# LCmeter0-LCD-8pinlcd-PIC_COMP.net
KiCad netlist of a schematic drawn in EAGLE
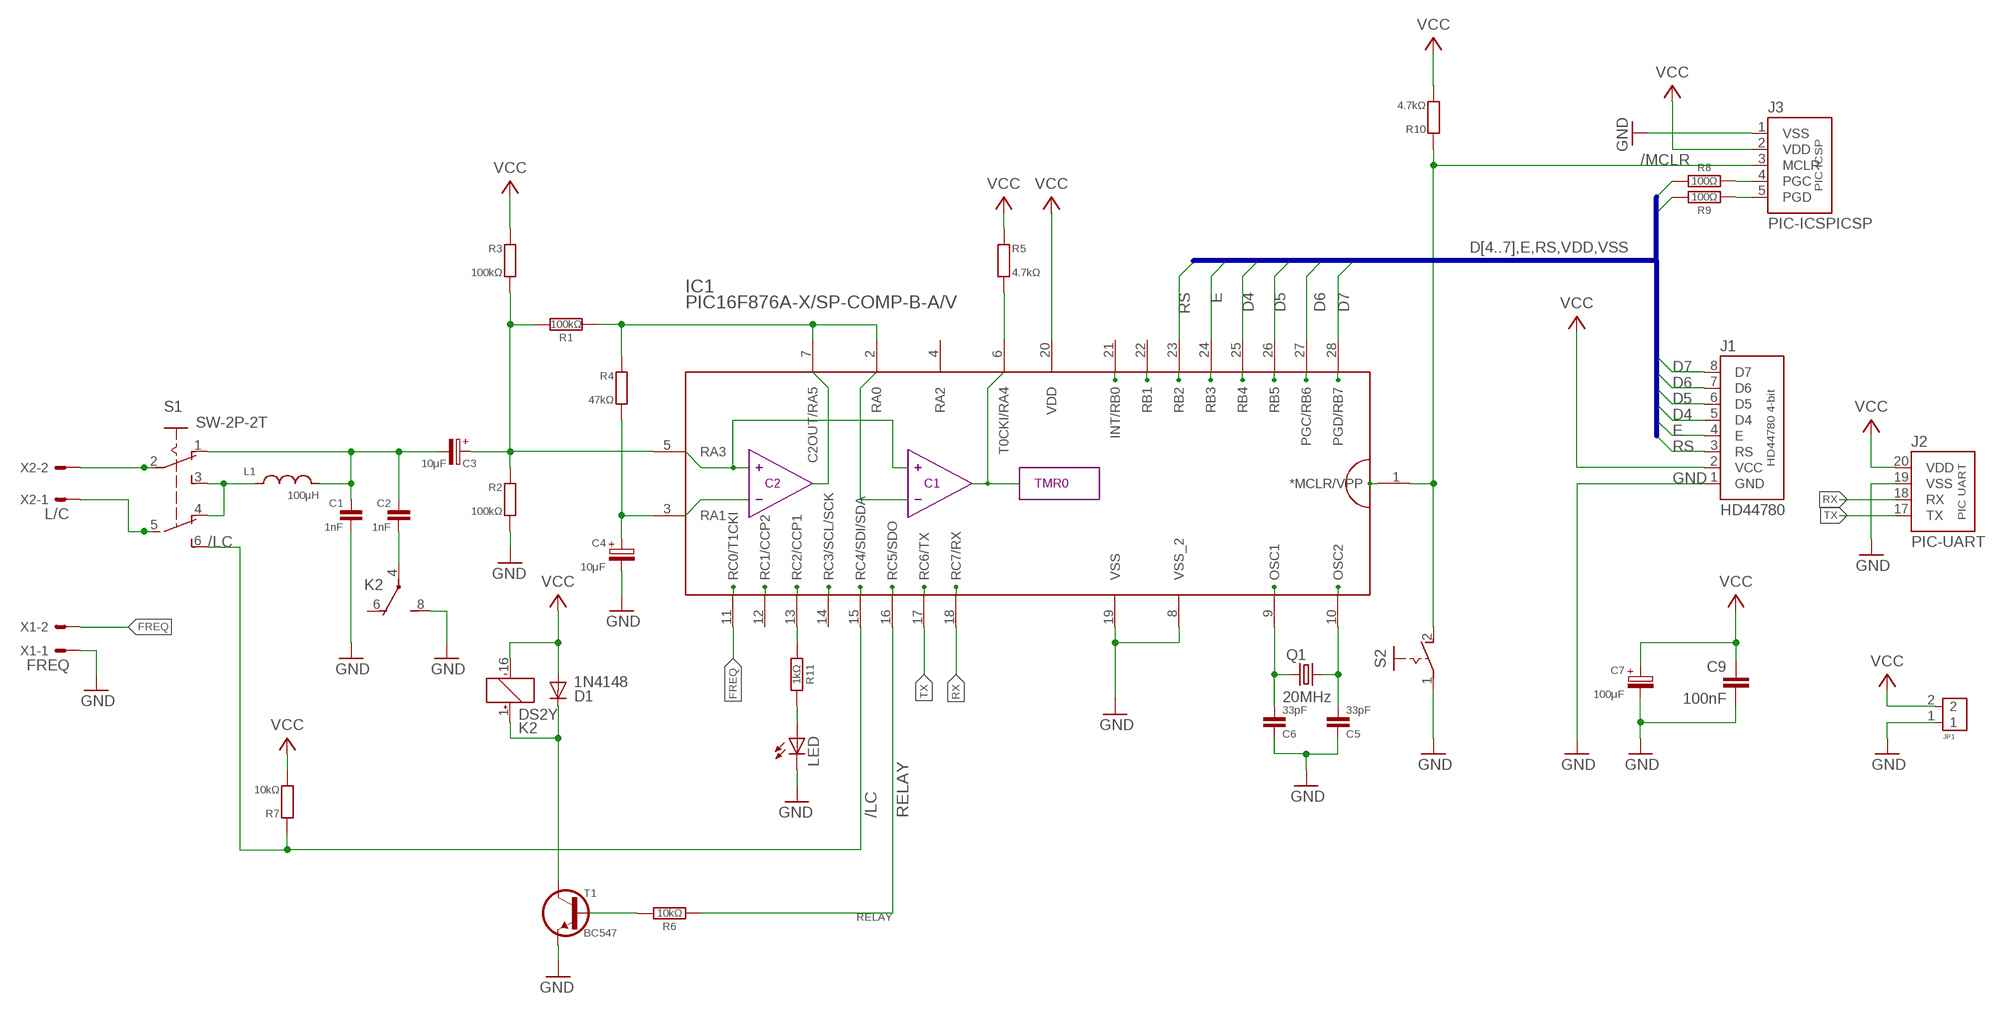
[diagram p0: schematic, sheet 1]

(export (version "E")
  (design (tool "Eeschema 10.0.6"))
  (components
    (comp (ref "C1")
      (value "1nF")
      (footprint "eagle-import:C050-020X036")
      (libsource (lib "eagle-import") (part "C050-020X036"))
    )
    (comp (ref "C2")
      (value "1nF")
      (footprint "eagle-import:C050-020X036")
      (libsource (lib "eagle-import") (part "C050-020X036"))
    )
    (comp (ref "C3")
      (value "10μF")
      (footprint "eagle-import:E2,5-4")
      (libsource (lib "eagle-import") (part "CPOL-HE2,5-4"))
    )
    (comp (ref "C4")
      (value "10μF")
      (footprint "eagle-import:E2,5-4")
      (libsource (lib "eagle-import") (part "CPOLE2,5-4"))
    )
    (comp (ref "C5")
      (value "33pF")
      (footprint "eagle-import:C025-020X036")
      (libsource (lib "eagle-import") (part "C025-020X036"))
    )
    (comp (ref "C6")
      (value "33pF")
      (footprint "eagle-import:C025-020X036")
      (libsource (lib "eagle-import") (part "C025-020X036"))
    )
    (comp (ref "C7")
      (value "100μF")
      (footprint "eagle-import:E2,5-5")
      (libsource (lib "eagle-import") (part "CPOLE2.5-5"))
    )
    (comp (ref "C9")
      (value "100nF")
      (footprint "eagle-import:C025-024X044")
      (libsource (lib "eagle-import") (part "C-EU025-024X044"))
    )
    (comp (ref "D1")
      (value "1N4148")
      (footprint "eagle-import:DO34-7")
      (libsource (lib "eagle-import") (part "1N414834-7"))
    )
    (comp (ref "IC1")
      (value "PIC16F876A-X/SP-COMP-B-A/V")
      (footprint "eagle-import:DIL28-3_V")
      (libsource (lib "eagle-import") (part "PIC16F876A-X/SP-COMP-B-A/V"))
    )
    (comp (ref "J1")
      (value "HD44780")
      (footprint "eagle-import:CONN-8P")
      (libsource (lib "eagle-import") (part "HD44780-4BIT-8PIN"))
    )
    (comp (ref "J2")
      (value "PIC-UART")
      (footprint "eagle-import:PIC-UART")
      (libsource (lib "eagle-import") (part "PIC-UART"))
    )
    (comp (ref "J3")
      (value "PIC-ICSPICSP")
      (footprint "eagle-import:PIC-ICSP")
      (libsource (lib "eagle-import") (part "PIC-ICSPICSP"))
    )
    (comp (ref "JP1")
      (value "CONN-2P2P/V")
      (footprint "eagle-import:CONN-2P-V")
      (libsource (lib "eagle-import") (part "CONN-2P2P/V"))
    )
    (comp (ref "K2")
      (value "DS2Y")
      (footprint "eagle-import:DS2Y")
      (fields (field (name "MPN") "DS2Y-S-DC5V"))
      (libsource (lib "eagle-import") (part "DS2Y-S-DC5V"))
    )
    (comp (ref "L1")
      (value "100µH")
      (footprint "eagle-import:L-02_5V")
      (libsource (lib "eagle-import") (part "L-SHORT02/5"))
    )
    (comp (ref "LED")
      (value "TLLG4400")
      (footprint "eagle-import:LED3MM")
      (fields (field (name "MF") "VISHAY SEMICONDUCTOR"))
      (libsource (lib "eagle-import") (part "TLLG4400"))
    )
    (comp (ref "Q1")
      (value "20MHz")
      (footprint "eagle-import:HC49")
      (libsource (lib "eagle-import") (part "CRYSTALHC49"))
    )
    (comp (ref "R1")
      (value "100kΩ")
      (footprint "eagle-import:0202_7")
      (libsource (lib "eagle-import") (part "R-H0202/7"))
    )
    (comp (ref "R2")
      (value "100kΩ")
      (footprint "eagle-import:0202_7")
      (libsource (lib "eagle-import") (part "R0202/7"))
    )
    (comp (ref "R3")
      (value "100kΩ")
      (footprint "eagle-import:0202_7")
      (libsource (lib "eagle-import") (part "R0202/7"))
    )
    (comp (ref "R4")
      (value "47kΩ")
      (footprint "eagle-import:0202_7")
      (libsource (lib "eagle-import") (part "R0202/7"))
    )
    (comp (ref "R5")
      (value "4.7kΩ")
      (footprint "eagle-import:0202_7")
      (libsource (lib "eagle-import") (part "R0202/7"))
    )
    (comp (ref "R6")
      (value "10kΩ")
      (footprint "eagle-import:0202_7")
      (libsource (lib "eagle-import") (part "R-H0202/7"))
    )
    (comp (ref "R7")
      (value "10kΩ")
      (footprint "eagle-import:0202_10")
      (libsource (lib "eagle-import") (part "R0202/10"))
    )
    (comp (ref "R8")
      (value "100Ω")
      (footprint "eagle-import:0202_5")
      (libsource (lib "eagle-import") (part "R-H0202/5"))
    )
    (comp (ref "R9")
      (value "100Ω")
      (footprint "eagle-import:0202_5")
      (libsource (lib "eagle-import") (part "R-H0202/5"))
    )
    (comp (ref "R10")
      (value "4.7kΩ")
      (footprint "eagle-import:0202_7")
      (libsource (lib "eagle-import") (part "R0202/7"))
    )
    (comp (ref "R11")
      (value "1kΩ")
      (footprint "eagle-import:0202_5")
      (libsource (lib "eagle-import") (part "R-H0202/5"))
    )
    (comp (ref "S1")
      (value "SW-2P-2T")
      (footprint "eagle-import:SLSW-2P2T")
      (libsource (lib "eagle-import") (part "SW-2P-2T"))
    )
    (comp (ref "S2")
      (value "PB-1P-1T")
      (footprint "eagle-import:PB-1P1T")
      (libsource (lib "eagle-import") (part "PB-1P-1T"))
    )
    (comp (ref "T1")
      (value "BC547")
      (footprint "eagle-import:TO92-CBE-A")
      (libsource (lib "eagle-import") (part "BC547CBE-A"))
    )
    (comp (ref "X1")
      (value "FREQ")
      (footprint "eagle-import:70543-02")
      (libsource (lib "eagle-import") (part "C-GRID-02-70543"))
    )
    (comp (ref "X2")
      (value "L/C")
      (footprint "eagle-import:70543-02")
      (libsource (lib "eagle-import") (part "C-GRID-02-70543"))
    )
  )
  (nets
    (net (code "3") (name "/D4") (class "Default")
      (node (ref "IC1") (pin "25") (pinfunction "RB4_25") (pintype "passive"))
      (node (ref "J1") (pin "5") (pinfunction "D4_5") (pintype "passive"))
    )
    (net (code "4") (name "/D5") (class "Default")
      (node (ref "IC1") (pin "26") (pinfunction "RB5_26") (pintype "passive"))
      (node (ref "J1") (pin "6") (pinfunction "D5_6") (pintype "passive"))
    )
    (net (code "5") (name "/D6") (class "Default")
      (node (ref "IC1") (pin "27") (pinfunction "PGC/RB6_27") (pintype "passive"))
      (node (ref "J1") (pin "7") (pinfunction "D6_7") (pintype "passive"))
      (node (ref "R9") (pin "1") (pinfunction "1_1") (pintype "passive"))
    )
    (net (code "6") (name "/D7") (class "Default")
      (node (ref "IC1") (pin "28") (pinfunction "PGD/RB7_28") (pintype "passive"))
      (node (ref "J1") (pin "8") (pinfunction "D7_8") (pintype "passive"))
      (node (ref "R8") (pin "1") (pinfunction "1_1") (pintype "passive"))
    )
    (net (code "7") (name "/E") (class "Default")
      (node (ref "IC1") (pin "24") (pinfunction "RB3_24") (pintype "passive"))
      (node (ref "J1") (pin "4") (pinfunction "E_4") (pintype "passive"))
    )
    (net (code "8") (name "/RELAY") (class "Default")
      (node (ref "IC1") (pin "16") (pinfunction "RC5/SDO_16") (pintype "passive"))
      (node (ref "R6") (pin "2") (pinfunction "2_2") (pintype "passive"))
    )
    (net (code "9") (name "/RS") (class "Default")
      (node (ref "IC1") (pin "23") (pinfunction "RB2_23") (pintype "passive"))
      (node (ref "J1") (pin "3") (pinfunction "RS_3") (pintype "passive"))
    )
    (net (code "11") (name "/{slash}LC") (class "Default")
      (node (ref "IC1") (pin "15") (pinfunction "RC4/SDI/SDA_15") (pintype "passive"))
      (node (ref "R7") (pin "1") (pinfunction "1_1") (pintype "passive"))
      (node (ref "S1") (pin "6") (pinfunction "S1_6") (pintype "passive"))
    )
    (net (code "12") (name "/{slash}MCLR") (class "Default")
      (node (ref "IC1") (pin "1") (pinfunction "*MCLR/VPP_1") (pintype "passive"))
      (node (ref "J3") (pin "3") (pinfunction "MCLR_3") (pintype "passive"))
      (node (ref "R10") (pin "1") (pinfunction "1_1") (pintype "passive"))
      (node (ref "S2") (pin "2") (pinfunction "S_2") (pintype "passive"))
    )
    (net (code "13") (name "FREQ") (class "Default")
      (node (ref "IC1") (pin "11") (pinfunction "RC0/T1CKI_11") (pintype "passive"))
      (node (ref "X1") (pin "2") (pinfunction "S_2") (pintype "passive"))
    )
    (net (code "14") (name "GND") (class "Default")
      (node (ref "C1") (pin "2") (pinfunction "2_2") (pintype "passive"))
      (node (ref "C4") (pin "-") (pinfunction "-_-") (pintype "passive"))
      (node (ref "C5") (pin "1") (pinfunction "1_1") (pintype "passive"))
      (node (ref "C6") (pin "1") (pinfunction "1_1") (pintype "passive"))
      (node (ref "C7") (pin "-") (pinfunction "-_-") (pintype "passive"))
      (node (ref "C9") (pin "2") (pinfunction "2_2") (pintype "passive"))
      (node (ref "IC1") (pin "19") (pinfunction "VSS_19") (pintype "passive"))
      (node (ref "IC1") (pin "8") (pinfunction "VSS_2_8") (pintype "passive"))
      (node (ref "J1") (pin "1") (pinfunction "GND_1") (pintype "passive"))
      (node (ref "J2") (pin "19") (pinfunction "VSS_19") (pintype "passive"))
      (node (ref "J3") (pin "1") (pinfunction "VSS_1") (pintype "passive"))
      (node (ref "JP1") (pin "1") (pinfunction "1_1") (pintype "bidirectional"))
      (node (ref "K2") (pin "8") (pinfunction "S_8") (pintype "passive"))
      (node (ref "LED") (pin "K") (pinfunction "C_K") (pintype "passive"))
      (node (ref "R2") (pin "2") (pinfunction "2_2") (pintype "passive"))
      (node (ref "S2") (pin "1") (pinfunction "P_1") (pintype "passive"))
      (node (ref "T1") (pin "E") (pinfunction "E_E") (pintype "passive"))
      (node (ref "X1") (pin "1") (pinfunction "S_1") (pintype "passive"))
    )
    (net (code "15") (name "Net-(IC1-C2OUT{slash}RA5)") (class "Default")
      (node (ref "IC1") (pin "2") (pinfunction "RA0_2") (pintype "passive"))
      (node (ref "IC1") (pin "7") (pinfunction "C2OUT/RA5_7") (pintype "passive"))
      (node (ref "R1") (pin "1") (pinfunction "1_1") (pintype "passive"))
      (node (ref "R4") (pin "1") (pinfunction "1_1") (pintype "passive"))
    )
    (net (code "16") (name "Net-(IC1-OSC1)") (class "Default")
      (node (ref "C6") (pin "2") (pinfunction "2_2") (pintype "passive"))
      (node (ref "IC1") (pin "9") (pinfunction "OSC1_9") (pintype "passive"))
      (node (ref "Q1") (pin "1") (pinfunction "1_1") (pintype "passive"))
    )
    (net (code "17") (name "Net-(IC1-OSC2)") (class "Default")
      (node (ref "C5") (pin "2") (pinfunction "2_2") (pintype "passive"))
      (node (ref "IC1") (pin "10") (pinfunction "OSC2_10") (pintype "passive"))
      (node (ref "Q1") (pin "2") (pinfunction "2_2") (pintype "passive"))
    )
    (net (code "18") (name "Net-(IC1-RA1)") (class "Default")
      (node (ref "C4") (pin "+") (pinfunction "+_+") (pintype "passive"))
      (node (ref "IC1") (pin "3") (pinfunction "RA1_3") (pintype "passive"))
      (node (ref "R4") (pin "2") (pinfunction "2_2") (pintype "passive"))
    )
    (net (code "19") (name "Net-(IC1-RA3)") (class "Default")
      (node (ref "C3") (pin "+") (pinfunction "+_+") (pintype "passive"))
      (node (ref "IC1") (pin "5") (pinfunction "RA3_5") (pintype "passive"))
      (node (ref "R1") (pin "2") (pinfunction "2_2") (pintype "passive"))
      (node (ref "R2") (pin "1") (pinfunction "1_1") (pintype "passive"))
      (node (ref "R3") (pin "2") (pinfunction "2_2") (pintype "passive"))
    )
    (net (code "20") (name "Net-(IC1-RC2{slash}CCP1)") (class "Default")
      (node (ref "IC1") (pin "13") (pinfunction "RC2/CCP1_13") (pintype "passive"))
      (node (ref "R11") (pin "2") (pinfunction "2_2") (pintype "passive"))
    )
    (net (code "21") (name "Net-(IC1-T0CKI{slash}RA4)") (class "Default")
      (node (ref "IC1") (pin "6") (pinfunction "T0CKI/RA4_6") (pintype "passive"))
      (node (ref "R5") (pin "2") (pinfunction "2_2") (pintype "passive"))
    )
    (net (code "22") (name "Net-(J3-PGC)") (class "Default")
      (node (ref "J3") (pin "4") (pinfunction "PGC_4") (pintype "passive"))
      (node (ref "R8") (pin "2") (pinfunction "2_2") (pintype "passive"))
    )
    (net (code "23") (name "Net-(J3-PGD)") (class "Default")
      (node (ref "J3") (pin "5") (pinfunction "PGD_5") (pintype "passive"))
      (node (ref "R9") (pin "2") (pinfunction "2_2") (pintype "passive"))
    )
    (net (code "24") (name "Net-(K2A-+)") (class "Default")
      (node (ref "D1") (pin "C") (pinfunction "C_C") (pintype "passive"))
      (node (ref "K2") (pin "1") (pinfunction "+_1") (pintype "passive"))
      (node (ref "T1") (pin "C") (pinfunction "C_C") (pintype "passive"))
    )
    (net (code "25") (name "Net-(K2B-P)") (class "Default")
      (node (ref "C2") (pin "2") (pinfunction "2_2") (pintype "passive"))
      (node (ref "K2") (pin "4") (pinfunction "P_4") (pintype "passive"))
    )
    (net (code "26") (name "Net-(LED-PadA)") (class "Default")
      (node (ref "LED") (pin "A") (pinfunction "A_A") (pintype "passive"))
      (node (ref "R11") (pin "1") (pinfunction "1_1") (pintype "passive"))
    )
    (net (code "27") (name "Net-(R6-Pad1)") (class "Default")
      (node (ref "R6") (pin "1") (pinfunction "1_1") (pintype "passive"))
      (node (ref "T1") (pin "B") (pinfunction "B_B") (pintype "passive"))
    )
    (net (code "28") (name "Net-(S1-O)") (class "Default")
      (node (ref "C1") (pin "1") (pinfunction "1_1") (pintype "passive"))
      (node (ref "C2") (pin "1") (pinfunction "1_1") (pintype "passive"))
      (node (ref "C3") (pin "-") (pinfunction "-_-") (pintype "passive"))
      (node (ref "L1") (pin "2") (pinfunction "2_2") (pintype "passive"))
      (node (ref "S1") (pin "1") (pinfunction "O_1") (pintype "passive"))
    )
    (net (code "29") (name "Net-(S1-O1)") (class "Default")
      (node (ref "L1") (pin "1") (pinfunction "1_1") (pintype "passive"))
      (node (ref "S1") (pin "3") (pinfunction "S_3") (pintype "passive"))
      (node (ref "S1") (pin "4") (pinfunction "O1_4") (pintype "passive"))
    )
    (net (code "30") (name "Net-(S1-P)") (class "Default")
      (node (ref "S1") (pin "2") (pinfunction "P_2") (pintype "passive"))
      (node (ref "X2") (pin "2") (pinfunction "S_2") (pintype "passive"))
    )
    (net (code "31") (name "Net-(S1-P1)") (class "Default")
      (node (ref "S1") (pin "5") (pinfunction "P1_5") (pintype "passive"))
      (node (ref "X2") (pin "1") (pinfunction "S_1") (pintype "passive"))
    )
    (net (code "32") (name "RX") (class "Default")
      (node (ref "IC1") (pin "18") (pinfunction "RC7/RX_18") (pintype "passive"))
      (node (ref "J2") (pin "18") (pinfunction "RX_18") (pintype "passive"))
    )
    (net (code "33") (name "TX") (class "Default")
      (node (ref "IC1") (pin "17") (pinfunction "RC6/TX_17") (pintype "passive"))
      (node (ref "J2") (pin "17") (pinfunction "TX_17") (pintype "passive"))
    )
    (net (code "34") (name "VCC") (class "Default")
      (node (ref "C7") (pin "+") (pinfunction "+_+") (pintype "passive"))
      (node (ref "C9") (pin "1") (pinfunction "1_1") (pintype "passive"))
      (node (ref "D1") (pin "A") (pinfunction "A_A") (pintype "passive"))
      (node (ref "IC1") (pin "20") (pinfunction "VDD_20") (pintype "passive"))
      (node (ref "J1") (pin "2") (pinfunction "VCC_2") (pintype "passive"))
      (node (ref "J2") (pin "20") (pinfunction "VDD_20") (pintype "passive"))
      (node (ref "J3") (pin "2") (pinfunction "VDD_2") (pintype "passive"))
      (node (ref "JP1") (pin "2") (pinfunction "2_2") (pintype "bidirectional"))
      (node (ref "K2") (pin "16") (pinfunction "-_16") (pintype "passive"))
      (node (ref "R10") (pin "2") (pinfunction "2_2") (pintype "passive"))
      (node (ref "R3") (pin "1") (pinfunction "1_1") (pintype "passive"))
      (node (ref "R5") (pin "1") (pinfunction "1_1") (pintype "passive"))
      (node (ref "R7") (pin "2") (pinfunction "2_2") (pintype "passive"))
    )
    (net (code "35") (name "unconnected-(IC1-INT{slash}RB0-Pad21)") (class "Default")
      (node (ref "IC1") (pin "21") (pinfunction "INT/RB0_21") (pintype "passive"))
    )
    (net (code "36") (name "unconnected-(IC1-RA2-Pad4)") (class "Default")
      (node (ref "IC1") (pin "4") (pinfunction "RA2_4") (pintype "passive"))
    )
    (net (code "37") (name "unconnected-(IC1-RB1-Pad22)") (class "Default")
      (node (ref "IC1") (pin "22") (pinfunction "RB1_22") (pintype "passive"))
    )
    (net (code "38") (name "unconnected-(IC1-RC1{slash}CCP2-Pad12)") (class "Default")
      (node (ref "IC1") (pin "12") (pinfunction "RC1/CCP2_12") (pintype "passive"))
    )
    (net (code "39") (name "unconnected-(IC1-RC3{slash}SCL{slash}SCK-Pad14)") (class "Default")
      (node (ref "IC1") (pin "14") (pinfunction "RC3/SCL/SCK_14") (pintype "passive"))
    )
    (net (code "40") (name "unconnected-(K2B-O-Pad6)") (class "Default")
      (node (ref "K2") (pin "6") (pinfunction "O_6") (pintype "passive"))
    )
  )
)
